# 2025_08_23_leds.net
KiCad netlist of a schematic drawn in EasyEDA Pro
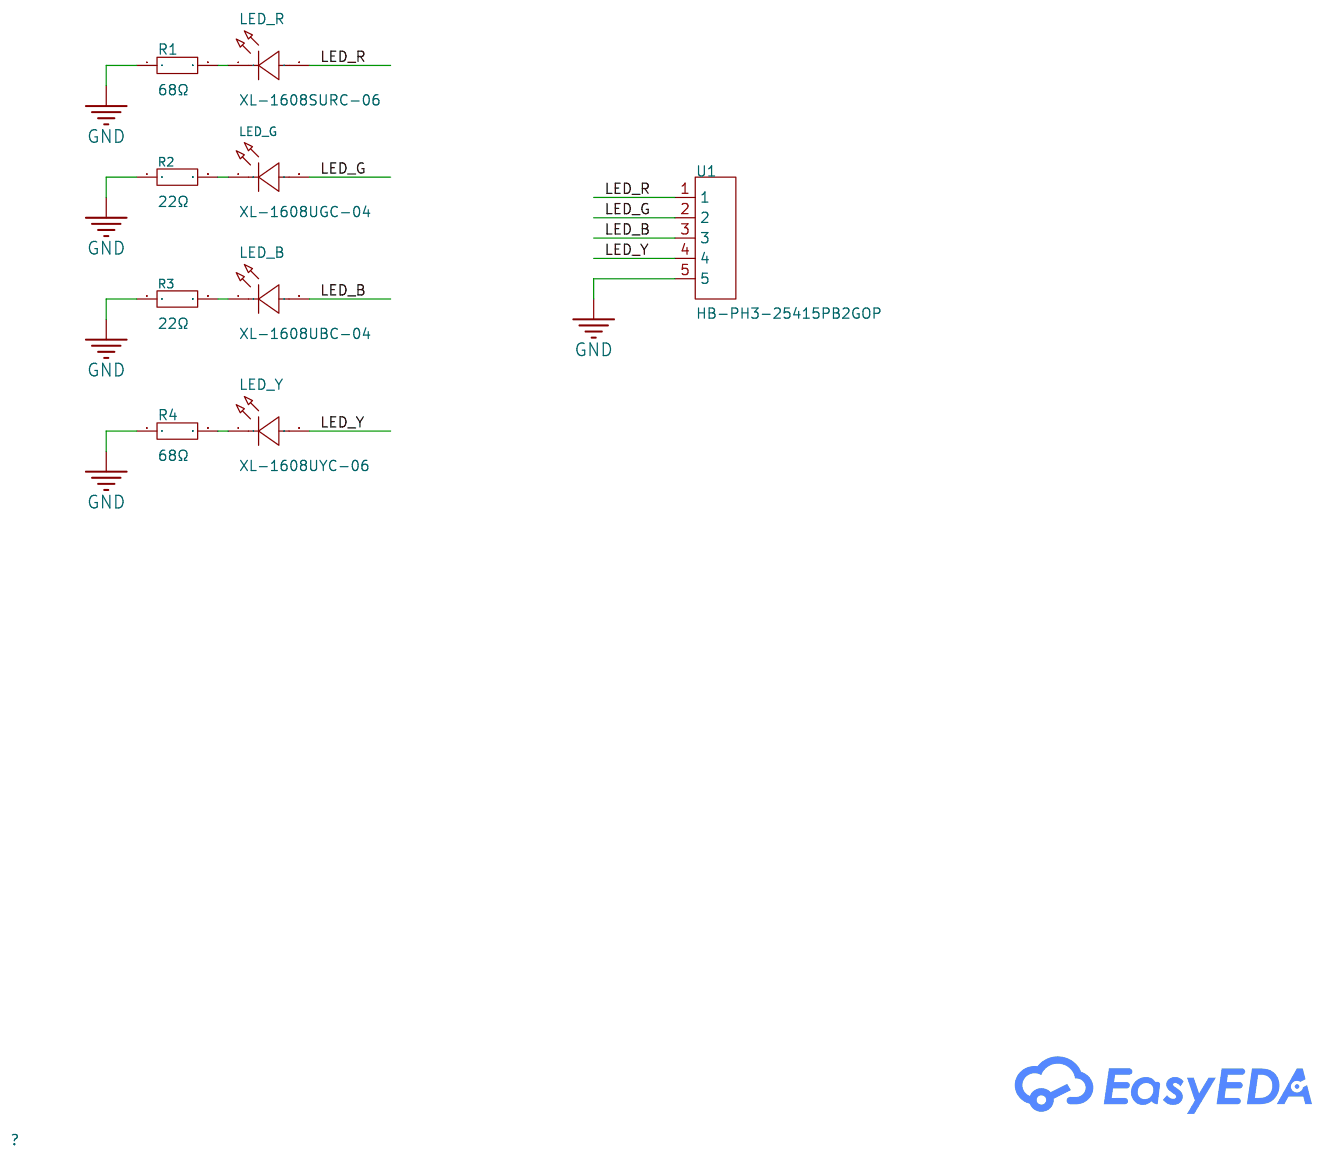
[diagram p0: schematic sheet]

(export (version "E")
  (design (tool "Eeschema 10.0.6"))
  (components
    (comp (ref "LED_B")
      (value "XL-1608UBC-04")
      (footprint "easyedapro:LED0603-RD_BLUE")
      (fields (field (name "Manufacturer") "XINGLIGHT(成兴光)"))
      (libsource (lib "easyedapro") (part "XL-1608UBC-04"))
    )
    (comp (ref "LED_G")
      (value "XL-1608UGC-04")
      (footprint "easyedapro:LED0603-RD_GREEN")
      (fields (field (name "Manufacturer") "XINGLIGHT(成兴光)"))
      (libsource (lib "easyedapro") (part "XL-1608UGC-04"))
    )
    (comp (ref "LED_R")
      (value "XL-1608SURC-06")
      (footprint "easyedapro:LED0603-RD_RED")
      (fields (field (name "Manufacturer") "XINGLIGHT(成兴光)"))
      (libsource (lib "easyedapro") (part "XL-1608SURC-06"))
    )
    (comp (ref "LED_Y")
      (value "XL-1608UYC-06")
      (footprint "easyedapro:LED0603-RD-YELLOW")
      (fields (field (name "Manufacturer") "XINGLIGHT(成兴光)"))
      (libsource (lib "easyedapro") (part "XL-1608UYC-06"))
    )
    (comp (ref "R1")
      (value "68Ω")
      (footprint "easyedapro:R0402")
      (fields (field (name "Manufacturer Part") "RC0402FR-0768RL") (field (name "Manufacturer") "YAGEO(国巨)"))
      (libsource (lib "easyedapro") (part "RC0402FR-0768RL"))
    )
    (comp (ref "R2")
      (value "22Ω")
      (footprint "easyedapro:R0402")
      (fields
        (field (name "Manufacturer Part") "0402WGF220JTCE")
        (field (name "Manufacturer") "UNI-ROYAL(厚声)")
      )
      (libsource (lib "easyedapro") (part "0402WGF220JTCE"))
    )
    (comp (ref "R3")
      (value "22Ω")
      (footprint "easyedapro:R0402")
      (fields
        (field (name "Manufacturer Part") "0402WGF220JTCE")
        (field (name "Manufacturer") "UNI-ROYAL(厚声)")
      )
      (libsource (lib "easyedapro") (part "0402WGF220JTCE"))
    )
    (comp (ref "R4")
      (value "68Ω")
      (footprint "easyedapro:R0402")
      (fields (field (name "Manufacturer Part") "RC0402FR-0768RL") (field (name "Manufacturer") "YAGEO(国巨)"))
      (libsource (lib "easyedapro") (part "RC0402FR-0768RL"))
    )
    (comp (ref "U1")
      (value "HB-PH3-25415PB2GOP")
      (footprint "easyedapro:HDR-TH_5P-P2.54-V-M")
      (fields (field (name "Manufacturer") "HANBO(汉博)"))
      (libsource (lib "easyedapro") (part "HB-PH3-25415PB2GOP"))
    )
  )
  (nets
    (net (code "1") (name "/LED_B") (class "Default")
      (node (ref "LED_B") (pin "2") (pinfunction "A_2") (pintype "unspecified"))
      (node (ref "U1") (pin "3") (pinfunction "3_3") (pintype "unspecified"))
    )
    (net (code "2") (name "/LED_G") (class "Default")
      (node (ref "LED_G") (pin "2") (pinfunction "A_2") (pintype "input"))
      (node (ref "U1") (pin "2") (pinfunction "2_2") (pintype "unspecified"))
    )
    (net (code "3") (name "/LED_R") (class "Default")
      (node (ref "LED_R") (pin "2") (pinfunction "A_2") (pintype "unspecified"))
      (node (ref "U1") (pin "1") (pinfunction "1_1") (pintype "unspecified"))
    )
    (net (code "4") (name "/LED_Y") (class "Default")
      (node (ref "LED_Y") (pin "2") (pinfunction "A_2") (pintype "unspecified"))
      (node (ref "U1") (pin "4") (pinfunction "4_4") (pintype "unspecified"))
    )
    (net (code "5") (name "GND") (class "Default")
      (node (ref "R1") (pin "1") (pinfunction "1_1") (pintype "input"))
      (node (ref "R2") (pin "1") (pinfunction "1_1") (pintype "input"))
      (node (ref "R3") (pin "1") (pinfunction "1_1") (pintype "input"))
      (node (ref "R4") (pin "1") (pinfunction "1_1") (pintype "input"))
      (node (ref "U1") (pin "5") (pinfunction "5_5") (pintype "unspecified"))
    )
    (net (code "6") (name "Net-(LED_B-K)") (class "Default")
      (node (ref "LED_B") (pin "1") (pinfunction "K_1") (pintype "unspecified"))
      (node (ref "R3") (pin "2") (pinfunction "2_2") (pintype "input"))
    )
    (net (code "7") (name "Net-(LED_G-K)") (class "Default")
      (node (ref "LED_G") (pin "1") (pinfunction "K_1") (pintype "input"))
      (node (ref "R2") (pin "2") (pinfunction "2_2") (pintype "input"))
    )
    (net (code "8") (name "Net-(LED_R-K)") (class "Default")
      (node (ref "LED_R") (pin "1") (pinfunction "K_1") (pintype "unspecified"))
      (node (ref "R1") (pin "2") (pinfunction "2_2") (pintype "input"))
    )
    (net (code "9") (name "Net-(LED_Y-K)") (class "Default")
      (node (ref "LED_Y") (pin "1") (pinfunction "K_1") (pintype "unspecified"))
      (node (ref "R4") (pin "2") (pinfunction "2_2") (pintype "input"))
    )
  )
)
